# BTB_CONN.net
KiCad netlist of a schematic drawn in Altium Designer
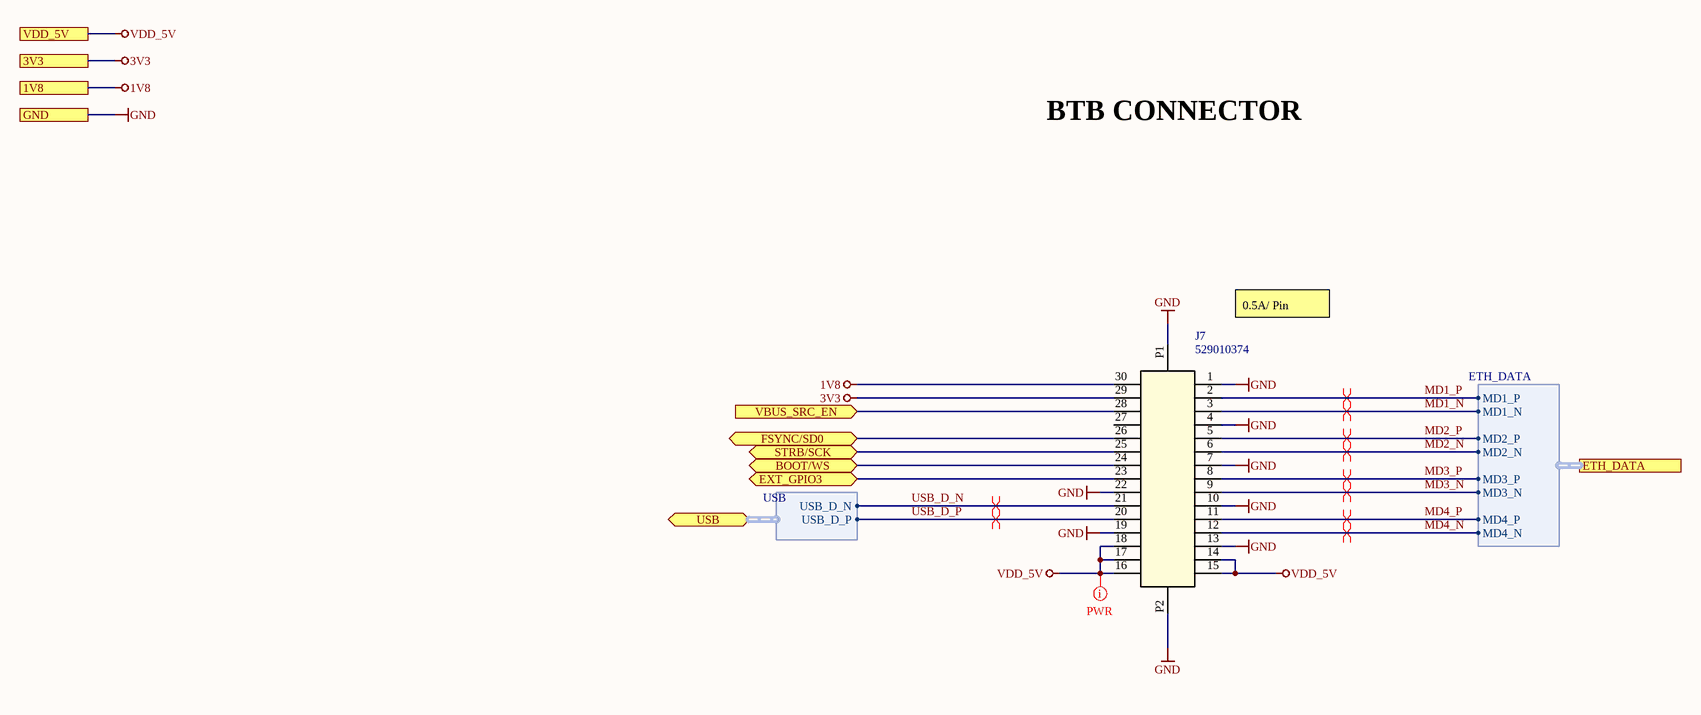
[diagram p0: BTB_CONN.SchDoc]

(export (version "E")
  (design (tool "Eeschema 10.0.6"))
  (components
    (comp (ref "J7")
      (value "529010374")
      (footprint "CON_529010374")
      (libsource (lib "Luxonis LLC") (part "529010374"))
    )
  )
  (nets
    (net (code "3") (name "/BOOT{slash}WS") (class "Default")
      (node (ref "J7") (pin "24") (pinfunction "24_24") (pintype "passive"))
    )
    (net (code "4") (name "/EXT_GPIO3") (class "Default")
      (node (ref "J7") (pin "23") (pinfunction "23_23") (pintype "passive"))
    )
    (net (code "5") (name "/FSYNC{slash}SD0") (class "Default")
      (node (ref "J7") (pin "26") (pinfunction "26_26") (pintype "passive"))
    )
    (net (code "6") (name "/MD1_N") (class "Default")
      (node (ref "J7") (pin "3") (pinfunction "3_3") (pintype "passive"))
    )
    (net (code "7") (name "/MD1_P") (class "Default")
      (node (ref "J7") (pin "2") (pinfunction "2_2") (pintype "passive"))
    )
    (net (code "8") (name "/MD2_N") (class "Default")
      (node (ref "J7") (pin "6") (pinfunction "6_6") (pintype "passive"))
    )
    (net (code "9") (name "/MD2_P") (class "Default")
      (node (ref "J7") (pin "5") (pinfunction "5_5") (pintype "passive"))
    )
    (net (code "10") (name "/MD3_N") (class "Default")
      (node (ref "J7") (pin "9") (pinfunction "9_9") (pintype "passive"))
    )
    (net (code "11") (name "/MD3_P") (class "Default")
      (node (ref "J7") (pin "8") (pinfunction "8_8") (pintype "passive"))
    )
    (net (code "12") (name "/MD4_N") (class "Default")
      (node (ref "J7") (pin "12") (pinfunction "12_12") (pintype "passive"))
    )
    (net (code "13") (name "/MD4_P") (class "Default")
      (node (ref "J7") (pin "11") (pinfunction "11_11") (pintype "passive"))
    )
    (net (code "14") (name "/STRB{slash}SCK") (class "Default")
      (node (ref "J7") (pin "25") (pinfunction "25_25") (pintype "passive"))
    )
    (net (code "15") (name "/USB_D_N") (class "Default")
      (node (ref "J7") (pin "21") (pinfunction "21_21") (pintype "passive"))
    )
    (net (code "16") (name "/USB_D_P") (class "Default")
      (node (ref "J7") (pin "20") (pinfunction "20_20") (pintype "passive"))
    )
    (net (code "17") (name "/VBUS_SRC_EN") (class "Default")
      (node (ref "J7") (pin "28") (pinfunction "28_28") (pintype "passive"))
    )
    (net (code "20") (name "1V8") (class "Default")
      (node (ref "J7") (pin "30") (pinfunction "30_30") (pintype "passive"))
    )
    (net (code "21") (name "3V3") (class "Default")
      (node (ref "J7") (pin "29") (pinfunction "29_29") (pintype "passive"))
    )
    (net (code "22") (name "GND") (class "Default")
      (node (ref "J7") (pin "1") (pinfunction "1_1") (pintype "passive"))
      (node (ref "J7") (pin "10") (pinfunction "10_10") (pintype "passive"))
      (node (ref "J7") (pin "13") (pinfunction "13_13") (pintype "passive"))
      (node (ref "J7") (pin "19") (pinfunction "19_19") (pintype "passive"))
      (node (ref "J7") (pin "22") (pinfunction "22_22") (pintype "passive"))
      (node (ref "J7") (pin "4") (pinfunction "4_4") (pintype "passive"))
      (node (ref "J7") (pin "7") (pinfunction "7_7") (pintype "passive"))
      (node (ref "J7") (pin "P1") (pinfunction "P1_P1") (pintype "passive"))
      (node (ref "J7") (pin "P2") (pinfunction "P2_P2") (pintype "passive"))
    )
    (net (code "23") (name "VDD_5V") (class "Default")
      (node (ref "J7") (pin "14") (pinfunction "14_14") (pintype "passive"))
      (node (ref "J7") (pin "15") (pinfunction "15_15") (pintype "passive"))
      (node (ref "J7") (pin "16") (pinfunction "16_16") (pintype "passive"))
      (node (ref "J7") (pin "17") (pinfunction "17_17") (pintype "passive"))
      (node (ref "J7") (pin "18") (pinfunction "18_18") (pintype "passive"))
    )
    (net (code "24") (name "unconnected-(J7-Pad27)") (class "Default")
      (node (ref "J7") (pin "27") (pinfunction "27_27") (pintype "passive"))
    )
  )
)
